# go-booster.net
KiCad netlist of a schematic drawn in EAGLE
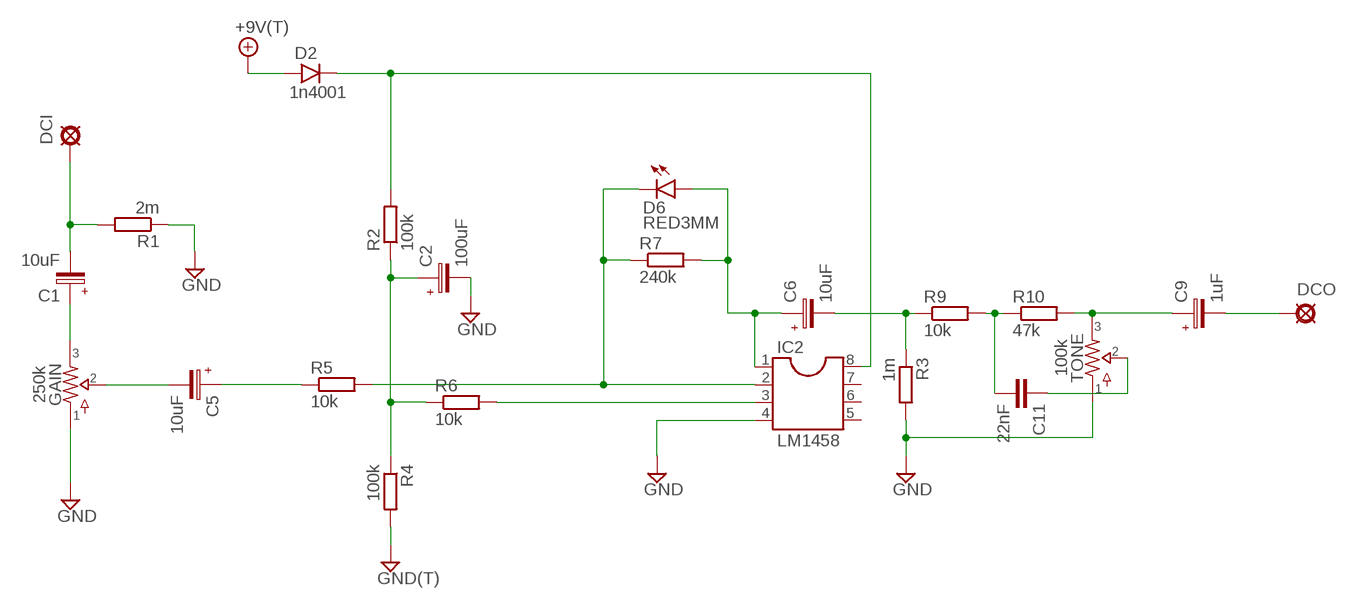
[diagram p0: schematic, sheet 1]

(export (version "E")
  (design (tool "Eeschema 10.0.6"))
  (components
    (comp (ref "+9V2")
      (value "+9V(T)")
      (footprint "eagle-import:SQUARE")
      (libsource (lib "eagle-import") (part "+9V(T)"))
    )
    (comp (ref "C1")
      (value "10uF")
      (footprint "eagle-import:050_020_1")
      (libsource (lib "eagle-import") (part "050-EU1"))
    )
    (comp (ref "C2")
      (value "100uF")
      (footprint "eagle-import:050_020_1")
      (libsource (lib "eagle-import") (part "050-EU1"))
    )
    (comp (ref "C5")
      (value "10uF")
      (footprint "eagle-import:050_020_1")
      (libsource (lib "eagle-import") (part "050-EU1"))
    )
    (comp (ref "C6")
      (value "10uF")
      (footprint "eagle-import:050_020_1")
      (libsource (lib "eagle-import") (part "050-EU1"))
    )
    (comp (ref "C9")
      (value "1uF")
      (footprint "eagle-import:050_020_1")
      (libsource (lib "eagle-import") (part "050-EU1"))
    )
    (comp (ref "C11")
      (value "22nF")
      (footprint "eagle-import:072X025")
      (libsource (lib "eagle-import") (part "072X0252"))
    )
    (comp (ref "D2")
      (value "1n4001")
      (footprint "eagle-import:DO41-4")
      (libsource (lib "eagle-import") (part "DO41.4"))
    )
    (comp (ref "D6")
      (value "RED3MM")
      (footprint "eagle-import:LED3MM")
      (libsource (lib "eagle-import") (part "LED3MM"))
    )
    (comp (ref "DCI")
      (value "IN")
      (footprint "eagle-import:OCTOGON")
      (libsource (lib "eagle-import") (part "PAD8"))
    )
    (comp (ref "DCO")
      (value "OUT")
      (footprint "eagle-import:OCTOGON")
      (libsource (lib "eagle-import") (part "PAD8"))
    )
    (comp (ref "GAIN")
      (value "250k")
      (footprint "eagle-import:16MM_CENTERMOUNT")
      (libsource (lib "eagle-import") (part "POTS"))
    )
    (comp (ref "GND11")
      (value "GND(T)")
      (footprint "eagle-import:SQUARE")
      (libsource (lib "eagle-import") (part "GND(T)"))
    )
    (comp (ref "IC2")
      (value "LM1458")
      (footprint "eagle-import:SOCKET-08")
      (libsource (lib "eagle-import") (part "DIL8S"))
    )
    (comp (ref "R1")
      (value "2m")
      (footprint "eagle-import:0207_10")
      (libsource (lib "eagle-import") (part "R-EU_0207/10"))
    )
    (comp (ref "R2")
      (value "100k")
      (footprint "eagle-import:0207_10")
      (libsource (lib "eagle-import") (part "R-EU_0207/10"))
    )
    (comp (ref "R3")
      (value "1m")
      (footprint "eagle-import:0207_10")
      (libsource (lib "eagle-import") (part "R-EU_0207/10"))
    )
    (comp (ref "R4")
      (value "100k")
      (footprint "eagle-import:0207_10")
      (libsource (lib "eagle-import") (part "R-EU_0207/10"))
    )
    (comp (ref "R5")
      (value "10k")
      (footprint "eagle-import:0207_10")
      (libsource (lib "eagle-import") (part "R-EU_0207/10"))
    )
    (comp (ref "R6")
      (value "10k")
      (footprint "eagle-import:0207_10")
      (libsource (lib "eagle-import") (part "R-EU_0207/10"))
    )
    (comp (ref "R7")
      (value "240k")
      (footprint "eagle-import:0207_10")
      (libsource (lib "eagle-import") (part "R-EU_0207/10"))
    )
    (comp (ref "R9")
      (value "10k")
      (footprint "eagle-import:0207_10")
      (libsource (lib "eagle-import") (part "R-EU_0207/10"))
    )
    (comp (ref "R10")
      (value "47k")
      (footprint "eagle-import:0207_10")
      (libsource (lib "eagle-import") (part "R-EU_0207/10"))
    )
    (comp (ref "TONE")
      (value "100k")
      (footprint "eagle-import:2262_TRIM")
      (libsource (lib "eagle-import") (part "POTSTRIM"))
    )
  )
  (nets
    (net (code "1") (name "+9V(T)") (class "Default")
      (node (ref "+9V2") (pin "1") (pinfunction "+9V_1") (pintype "power_in"))
      (node (ref "D2") (pin "A") (pinfunction "A_A") (pintype "passive"))
    )
    (net (code "2") (name "GND") (class "Default")
      (node (ref "C2") (pin "-") (pinfunction "-_-") (pintype "passive"))
      (node (ref "GAIN") (pin "1") (pinfunction "1_1") (pintype "passive"))
      (node (ref "GND11") (pin "1") (pinfunction "GND_1") (pintype "power_in"))
      (node (ref "IC2") (pin "4") (pinfunction "4_4") (pintype "passive"))
      (node (ref "R1") (pin "1") (pinfunction "1_1") (pintype "passive"))
      (node (ref "R3") (pin "2") (pinfunction "2_2") (pintype "passive"))
      (node (ref "R4") (pin "2") (pinfunction "2_2") (pintype "passive"))
      (node (ref "TONE") (pin "1") (pinfunction "1_1") (pintype "passive"))
    )
    (net (code "3") (name "Net-(C1-Pad+)") (class "Default")
      (node (ref "C1") (pin "+") (pinfunction "+_+") (pintype "passive"))
      (node (ref "GAIN") (pin "3") (pinfunction "3_3") (pintype "passive"))
    )
    (net (code "4") (name "Net-(C2-Pad+)") (class "Default")
      (node (ref "C2") (pin "+") (pinfunction "+_+") (pintype "passive"))
      (node (ref "R2") (pin "1") (pinfunction "1_1") (pintype "passive"))
      (node (ref "R4") (pin "1") (pinfunction "1_1") (pintype "passive"))
      (node (ref "R6") (pin "1") (pinfunction "1_1") (pintype "passive"))
    )
    (net (code "5") (name "Net-(C5-Pad+)") (class "Default")
      (node (ref "C5") (pin "+") (pinfunction "+_+") (pintype "passive"))
      (node (ref "R5") (pin "1") (pinfunction "1_1") (pintype "passive"))
    )
    (net (code "6") (name "Net-(C5-Pad-)") (class "Default")
      (node (ref "C5") (pin "-") (pinfunction "-_-") (pintype "passive"))
      (node (ref "GAIN") (pin "2") (pinfunction "2_2") (pintype "passive"))
    )
    (net (code "7") (name "Net-(C6-Pad+)") (class "Default")
      (node (ref "C6") (pin "+") (pinfunction "+_+") (pintype "passive"))
      (node (ref "D6") (pin "A") (pinfunction "A_A") (pintype "passive"))
      (node (ref "IC2") (pin "1") (pinfunction "1_1") (pintype "passive"))
      (node (ref "R7") (pin "2") (pinfunction "2_2") (pintype "passive"))
    )
    (net (code "8") (name "Net-(C6-Pad-)") (class "Default")
      (node (ref "C6") (pin "-") (pinfunction "-_-") (pintype "passive"))
      (node (ref "R3") (pin "1") (pinfunction "1_1") (pintype "passive"))
      (node (ref "R9") (pin "1") (pinfunction "1_1") (pintype "passive"))
    )
    (net (code "9") (name "Net-(C9-Pad+)") (class "Default")
      (node (ref "C9") (pin "+") (pinfunction "+_+") (pintype "passive"))
      (node (ref "R10") (pin "2") (pinfunction "2_2") (pintype "passive"))
      (node (ref "TONE") (pin "3") (pinfunction "3_3") (pintype "passive"))
    )
    (net (code "10") (name "Net-(C11-Pad1)") (class "Default")
      (node (ref "C11") (pin "1") (pinfunction "1_1") (pintype "passive"))
      (node (ref "TONE") (pin "2") (pinfunction "2_2") (pintype "passive"))
    )
    (net (code "11") (name "Net-(C11-Pad2)") (class "Default")
      (node (ref "C11") (pin "2") (pinfunction "2_2") (pintype "passive"))
      (node (ref "R10") (pin "1") (pinfunction "1_1") (pintype "passive"))
      (node (ref "R9") (pin "2") (pinfunction "2_2") (pintype "passive"))
    )
    (net (code "12") (name "Net-(D2-PadC)") (class "Default")
      (node (ref "D2") (pin "C") (pinfunction "C_C") (pintype "passive"))
      (node (ref "IC2") (pin "8") (pinfunction "8_8") (pintype "passive"))
      (node (ref "R2") (pin "2") (pinfunction "2_2") (pintype "passive"))
    )
    (net (code "13") (name "Net-(D6-C)") (class "Default")
      (node (ref "D6") (pin "K") (pinfunction "C_K") (pintype "passive"))
      (node (ref "IC2") (pin "2") (pinfunction "2_2") (pintype "passive"))
      (node (ref "R5") (pin "2") (pinfunction "2_2") (pintype "passive"))
      (node (ref "R7") (pin "1") (pinfunction "1_1") (pintype "passive"))
    )
    (net (code "14") (name "Net-(DCI-PAD)") (class "Default")
      (node (ref "C1") (pin "-") (pinfunction "-_-") (pintype "passive"))
      (node (ref "DCI") (pin "1") (pinfunction "PAD_1") (pintype "passive"))
      (node (ref "R1") (pin "2") (pinfunction "2_2") (pintype "passive"))
    )
    (net (code "15") (name "Net-(DCO-PAD)") (class "Default")
      (node (ref "C9") (pin "-") (pinfunction "-_-") (pintype "passive"))
      (node (ref "DCO") (pin "1") (pinfunction "PAD_1") (pintype "passive"))
    )
    (net (code "16") (name "Net-(IC2-Pad3)") (class "Default")
      (node (ref "IC2") (pin "3") (pinfunction "3_3") (pintype "passive"))
      (node (ref "R6") (pin "2") (pinfunction "2_2") (pintype "passive"))
    )
    (net (code "17") (name "unconnected-(IC2-Pad5)") (class "Default")
      (node (ref "IC2") (pin "5") (pinfunction "5_5") (pintype "passive"))
    )
    (net (code "18") (name "unconnected-(IC2-Pad6)") (class "Default")
      (node (ref "IC2") (pin "6") (pinfunction "6_6") (pintype "passive"))
    )
    (net (code "19") (name "unconnected-(IC2-Pad7)") (class "Default")
      (node (ref "IC2") (pin "7") (pinfunction "7_7") (pintype "passive"))
    )
  )
)
